# 19-AM64x-08.net
KiCad netlist of a schematic drawn in Altium Designer
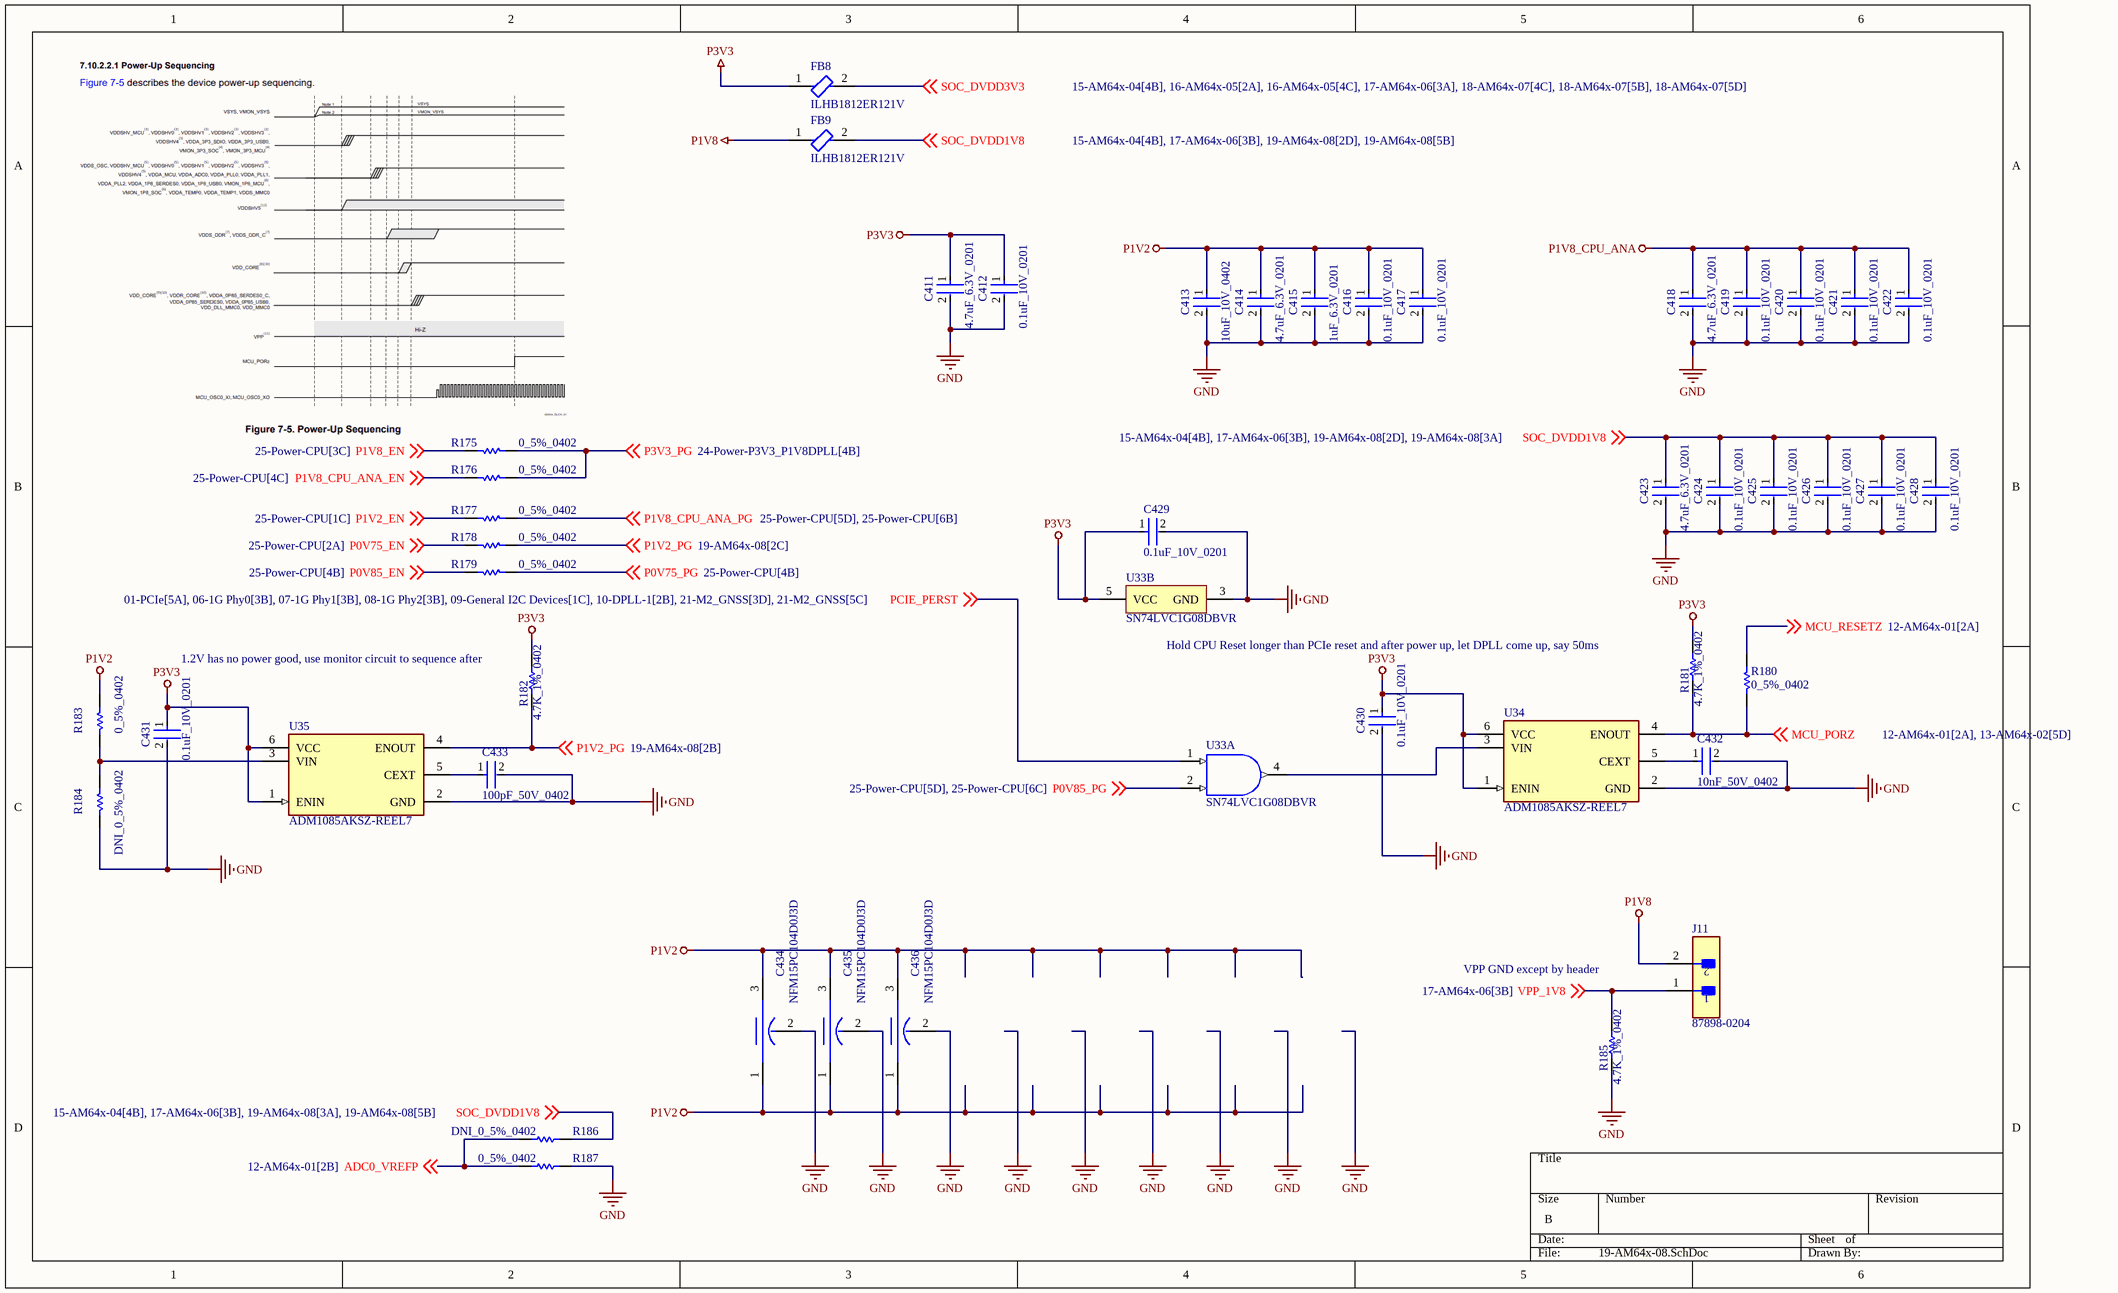
[diagram p0: 19-AM64x-08.SchDoc]

(export (version "E")
  (design (tool "Eeschema 10.0.6"))
  (components
    (comp (ref "C411")
      (value "4.7uF_6.3V_0201")
      (footprint "FP-GRM035-0_09-IPC_B")
      (description "Chip Multilayer Ceramic Capacitors for General Purpose, 0201, 4.7uF, X5R, 15%, 20%, 6.3V")
      (fields (field (name "TOLERANCE") "20%"))
      (libsource (lib "Altium Content Vault") (part "02cd4be3c70576c341d710602a673aa"))
    )
    (comp (ref "C412")
      (value "0.1uF_10V_0201")
      (footprint "FP-GRM033-0_03-IPC_C")
      (description "Chip Multilayer Ceramic Capacitors for General Purpose, 0201, 0.10uF, X5R, 15%, 10%, 10V")
      (fields (field (name "TOLERANCE") "10%") (field (name "VOLTAGE") "10V"))
      (libsource (lib "Altium Content Vault") (part "b4654b650e69147ec39a6b967a45e02"))
    )
    (comp (ref "C413")
      (value "10uF_10V_0402")
      (footprint "FP-CL05A106MP5NUNC-MFG")
      (description "CAP CER 10UF 10V X5R 0402")
      (fields
        (field (name "OCTOPART") "https://octopart.com/cl05a106mp5nunc-samsung-22457395")
        (field (name "TOLERANCE") "20%")
      )
      (libsource (lib "Altium Content Vault") (part "b4654b650e69147ec39a6b967a45e02"))
    )
    (comp (ref "C414")
      (value "4.7uF_6.3V_0201")
      (footprint "FP-GRM035-0_09-IPC_B")
      (description "Chip Multilayer Ceramic Capacitors for General Purpose, 0201, 4.7uF, X5R, 15%, 20%, 6.3V")
      (fields (field (name "TOLERANCE") "20%"))
      (libsource (lib "Altium Content Vault") (part "02cd4be3c70576c341d710602a673aa"))
    )
    (comp (ref "C415")
      (value "1uF_6.3V_0201")
      (footprint "FP-CL03-IPC_B")
      (description "Cap Ceramic 1uF 6.3V X5R ±20% Pad SMD 0201 +85°C T/R")
      (fields (field (name "TOLERANCE") "20%"))
      (libsource (lib "Altium Content Vault") (part "b4654b650e69147ec39a6b967a45e02"))
    )
    (comp (ref "C416")
      (value "0.1uF_10V_0201")
      (footprint "FP-GRM033-0_03-IPC_C")
      (description "Chip Multilayer Ceramic Capacitors for General Purpose, 0201, 0.10uF, X5R, 15%, 10%, 10V")
      (fields (field (name "TOLERANCE") "10%") (field (name "VOLTAGE") "10V"))
      (libsource (lib "Altium Content Vault") (part "b4654b650e69147ec39a6b967a45e02"))
    )
    (comp (ref "C417")
      (value "0.1uF_10V_0201")
      (footprint "FP-GRM033-0_03-IPC_C")
      (description "Chip Multilayer Ceramic Capacitors for General Purpose, 0201, 0.10uF, X5R, 15%, 10%, 10V")
      (fields (field (name "TOLERANCE") "10%") (field (name "VOLTAGE") "10V"))
      (libsource (lib "Altium Content Vault") (part "b4654b650e69147ec39a6b967a45e02"))
    )
    (comp (ref "C418")
      (value "4.7uF_6.3V_0201")
      (footprint "FP-GRM035-0_09-IPC_B")
      (description "Chip Multilayer Ceramic Capacitors for General Purpose, 0201, 4.7uF, X5R, 15%, 20%, 6.3V")
      (fields (field (name "TOLERANCE") "20%"))
      (libsource (lib "Altium Content Vault") (part "02cd4be3c70576c341d710602a673aa"))
    )
    (comp (ref "C419")
      (value "0.1uF_10V_0201")
      (footprint "FP-GRM033-0_03-IPC_C")
      (description "Chip Multilayer Ceramic Capacitors for General Purpose, 0201, 0.10uF, X5R, 15%, 10%, 10V")
      (fields (field (name "TOLERANCE") "10%") (field (name "VOLTAGE") "10V"))
      (libsource (lib "Altium Content Vault") (part "b4654b650e69147ec39a6b967a45e02"))
    )
    (comp (ref "C420")
      (value "0.1uF_10V_0201")
      (footprint "FP-GRM033-0_03-IPC_C")
      (description "Chip Multilayer Ceramic Capacitors for General Purpose, 0201, 0.10uF, X5R, 15%, 10%, 10V")
      (fields (field (name "TOLERANCE") "10%") (field (name "VOLTAGE") "10V"))
      (libsource (lib "Altium Content Vault") (part "b4654b650e69147ec39a6b967a45e02"))
    )
    (comp (ref "C421")
      (value "0.1uF_10V_0201")
      (footprint "FP-GRM033-0_03-IPC_C")
      (description "Chip Multilayer Ceramic Capacitors for General Purpose, 0201, 0.10uF, X5R, 15%, 10%, 10V")
      (fields (field (name "TOLERANCE") "10%") (field (name "VOLTAGE") "10V"))
      (libsource (lib "Altium Content Vault") (part "b4654b650e69147ec39a6b967a45e02"))
    )
    (comp (ref "C422")
      (value "0.1uF_10V_0201")
      (footprint "FP-GRM033-0_03-IPC_C")
      (description "Chip Multilayer Ceramic Capacitors for General Purpose, 0201, 0.10uF, X5R, 15%, 10%, 10V")
      (fields (field (name "TOLERANCE") "10%") (field (name "VOLTAGE") "10V"))
      (libsource (lib "Altium Content Vault") (part "b4654b650e69147ec39a6b967a45e02"))
    )
    (comp (ref "C423")
      (value "4.7uF_6.3V_0201")
      (footprint "FP-GRM035-0_09-IPC_B")
      (description "Chip Multilayer Ceramic Capacitors for General Purpose, 0201, 4.7uF, X5R, 15%, 20%, 6.3V")
      (fields (field (name "TOLERANCE") "20%"))
      (libsource (lib "Altium Content Vault") (part "02cd4be3c70576c341d710602a673aa"))
    )
    (comp (ref "C424")
      (value "0.1uF_10V_0201")
      (footprint "FP-GRM033-0_03-IPC_C")
      (description "Chip Multilayer Ceramic Capacitors for General Purpose, 0201, 0.10uF, X5R, 15%, 10%, 10V")
      (fields (field (name "TOLERANCE") "10%") (field (name "VOLTAGE") "10V"))
      (libsource (lib "Altium Content Vault") (part "b4654b650e69147ec39a6b967a45e02"))
    )
    (comp (ref "C425")
      (value "0.1uF_10V_0201")
      (footprint "FP-GRM033-0_03-IPC_C")
      (description "Chip Multilayer Ceramic Capacitors for General Purpose, 0201, 0.10uF, X5R, 15%, 10%, 10V")
      (fields (field (name "TOLERANCE") "10%") (field (name "VOLTAGE") "10V"))
      (libsource (lib "Altium Content Vault") (part "b4654b650e69147ec39a6b967a45e02"))
    )
    (comp (ref "C426")
      (value "0.1uF_10V_0201")
      (footprint "FP-GRM033-0_03-IPC_C")
      (description "Chip Multilayer Ceramic Capacitors for General Purpose, 0201, 0.10uF, X5R, 15%, 10%, 10V")
      (fields (field (name "TOLERANCE") "10%") (field (name "VOLTAGE") "10V"))
      (libsource (lib "Altium Content Vault") (part "b4654b650e69147ec39a6b967a45e02"))
    )
    (comp (ref "C427")
      (value "0.1uF_10V_0201")
      (footprint "FP-GRM033-0_03-IPC_C")
      (description "Chip Multilayer Ceramic Capacitors for General Purpose, 0201, 0.10uF, X5R, 15%, 10%, 10V")
      (fields (field (name "TOLERANCE") "10%") (field (name "VOLTAGE") "10V"))
      (libsource (lib "Altium Content Vault") (part "b4654b650e69147ec39a6b967a45e02"))
    )
    (comp (ref "C428")
      (value "0.1uF_10V_0201")
      (footprint "FP-GRM033-0_03-IPC_C")
      (description "Chip Multilayer Ceramic Capacitors for General Purpose, 0201, 0.10uF, X5R, 15%, 10%, 10V")
      (fields (field (name "TOLERANCE") "10%") (field (name "VOLTAGE") "10V"))
      (libsource (lib "Altium Content Vault") (part "b4654b650e69147ec39a6b967a45e02"))
    )
    (comp (ref "C429")
      (value "0.1uF_10V_0201")
      (footprint "FP-GRM033-0_03-IPC_C")
      (description "Chip Multilayer Ceramic Capacitors for General Purpose, 0201, 0.10uF, X5R, 15%, 10%, 10V")
      (fields (field (name "TOLERANCE") "10%") (field (name "VOLTAGE") "10V"))
      (libsource (lib "Altium Content Vault") (part "b4654b650e69147ec39a6b967a45e02"))
    )
    (comp (ref "C430")
      (value "0.1uF_10V_0201")
      (footprint "FP-GRM033-0_03-IPC_C")
      (description "Chip Multilayer Ceramic Capacitors for General Purpose, 0201, 0.10uF, X5R, 15%, 10%, 10V")
      (fields (field (name "TOLERANCE") "10%") (field (name "VOLTAGE") "10V"))
      (libsource (lib "Altium Content Vault") (part "b4654b650e69147ec39a6b967a45e02"))
    )
    (comp (ref "C431")
      (value "0.1uF_10V_0201")
      (footprint "FP-GRM033-0_03-IPC_C")
      (description "Chip Multilayer Ceramic Capacitors for General Purpose, 0201, 0.10uF, X5R, 15%, 10%, 10V")
      (fields (field (name "TOLERANCE") "10%") (field (name "VOLTAGE") "10V"))
      (libsource (lib "Altium Content Vault") (part "b4654b650e69147ec39a6b967a45e02"))
    )
    (comp (ref "C432")
      (value "10nF_50V_0402")
      (footprint "FP-CL165-IPC_C")
      (description "Cap Ceramic 10nF 50V X7R ±10% SMD 0402 +125°C Paper T/R")
      (fields (field (name "VOLTAGE") "50V") (field (name "TOLERANCE") "10%"))
      (libsource (lib "Altium Content Vault") (part "b4654b650e69147ec39a6b967a45e02"))
    )
    (comp (ref "C433")
      (value "100pF_50V_0402")
      (footprint "FP-C0402-BB-MFG")
      (description "CAP CER 100PF 50V C0G/NP0 0402")
      (fields (field (name "TOLERANCE") "0.02") (field (name "MANUFACTURER") "Kemet"))
      (libsource (lib "Altium Content Vault") (part "b4654b650e69147ec39a6b967a45e02"))
    )
    (comp (ref "C434")
      (value "NFM15PC104D0J3D")
      (footprint "FP-NFM15-0_1-MFG")
      (description "CAP FEEDTHRU 0.1UF 20% 6.3V 0402")
      (fields (field (name "TOLERANCE") "20%"))
      (libsource (lib "Altium Content Vault") (part "968ca41a07abfef6fd4f7114a56c54f"))
    )
    (comp (ref "C435")
      (value "NFM15PC104D0J3D")
      (footprint "FP-NFM15-0_1-MFG")
      (description "CAP FEEDTHRU 0.1UF 20% 6.3V 0402")
      (fields (field (name "TOLERANCE") "20%"))
      (libsource (lib "Altium Content Vault") (part "968ca41a07abfef6fd4f7114a56c54f"))
    )
    (comp (ref "C436")
      (value "NFM15PC104D0J3D")
      (footprint "FP-NFM15-0_1-MFG")
      (description "CAP FEEDTHRU 0.1UF 20% 6.3V 0402")
      (fields (field (name "TOLERANCE") "20%"))
      (libsource (lib "Altium Content Vault") (part "968ca41a07abfef6fd4f7114a56c54f"))
    )
    (comp (ref "FB8")
      (value "ILHB1812ER121V")
      (footprint "FP-ILHB1812-IPC_A")
      (description "ILHB1812ER121V Ferrite Beads Multi-Layer High Current 120Ohm 25% 100MHz 6A 20mOhm DCR 1812 T/R")
      (fields (field (name "TOLERANCE") "25%"))
      (libsource (lib "Altium Content Vault") (part "5f30dd21d616792df468990f7003faa"))
    )
    (comp (ref "FB9")
      (value "ILHB1812ER121V")
      (footprint "FP-ILHB1812-IPC_A")
      (description "ILHB1812ER121V Ferrite Beads Multi-Layer High Current 120Ohm 25% 100MHz 6A 20mOhm DCR 1812 T/R")
      (fields (field (name "TOLERANCE") "25%"))
      (libsource (lib "Altium Content Vault") (part "5f30dd21d616792df468990f7003faa"))
    )
    (comp (ref "J11")
      (value "87898-0204")
      (footprint "FP-87898-0204-MFG")
      (description "CONN BREAKAWAY SMD HDR 2POS")
      (libsource (lib "Altium Content Vault") (part "3bc925449376181038e59eaffc5286c"))
    )
    (comp (ref "R175")
      (value "0_5%_0402")
      (footprint "RESC1005X40X25LL10T10")
      (fields (field (name "MANUFACTURER") "KOA Speer") (field (name "PART NUMBER") "RK73Z1ETTP"))
      (libsource (lib "Altium Content Vault") (part "RES"))
    )
    (comp (ref "R176")
      (value "0_5%_0402")
      (footprint "RESC1005X40X25LL10T10")
      (fields (field (name "MANUFACTURER") "KOA Speer") (field (name "PART NUMBER") "RK73Z1ETTP"))
      (libsource (lib "Altium Content Vault") (part "RES"))
    )
    (comp (ref "R177")
      (value "0_5%_0402")
      (footprint "RESC1005X40X25LL10T10")
      (fields (field (name "MANUFACTURER") "KOA Speer") (field (name "PART NUMBER") "RK73Z1ETTP"))
      (libsource (lib "Altium Content Vault") (part "RES"))
    )
    (comp (ref "R178")
      (value "0_5%_0402")
      (footprint "RESC1005X40X25LL10T10")
      (fields (field (name "MANUFACTURER") "KOA Speer") (field (name "PART NUMBER") "RK73Z1ETTP"))
      (libsource (lib "Altium Content Vault") (part "RES"))
    )
    (comp (ref "R179")
      (value "0_5%_0402")
      (footprint "RESC1005X40X25LL10T10")
      (fields (field (name "MANUFACTURER") "KOA Speer") (field (name "PART NUMBER") "RK73Z1ETTP"))
      (libsource (lib "Altium Content Vault") (part "RES"))
    )
    (comp (ref "R180")
      (value "0_5%_0402")
      (footprint "RESC1005X40X25LL10T10")
      (fields (field (name "MANUFACTURER") "KOA Speer") (field (name "PART NUMBER") "RK73Z1ETTP"))
      (libsource (lib "Altium Content Vault") (part "RES"))
    )
    (comp (ref "R181")
      (value "4.7K_1%_0402")
      (footprint "RESC1005X40X25NL10T10")
      (fields (field (name "MANUFACTURER") "Bourns") (field (name "PART NUMBER") "CR0402-FX-4701GLF"))
      (libsource (lib "Altium Content Vault") (part "RES"))
    )
    (comp (ref "R182")
      (value "4.7K_1%_0402")
      (footprint "RESC1005X40X25NL10T10")
      (fields (field (name "MANUFACTURER") "Bourns") (field (name "PART NUMBER") "CR0402-FX-4701GLF"))
      (libsource (lib "Altium Content Vault") (part "RES"))
    )
    (comp (ref "R183")
      (value "0_5%_0402")
      (footprint "RESC1005X40X25LL10T10")
      (fields (field (name "MANUFACTURER") "KOA Speer") (field (name "PART NUMBER") "RK73Z1ETTP"))
      (libsource (lib "Altium Content Vault") (part "RES"))
    )
    (comp (ref "R184")
      (value "DNI_0_5%_0402")
      (footprint "RESC1005X40X25LL10T10")
      (fields (field (name "MANUFACTURER") "KOA Speer") (field (name "PART NUMBER") "RK73Z1ETTP"))
      (libsource (lib "Altium Content Vault") (part "RES"))
    )
    (comp (ref "R185")
      (value "4.7K_1%_0402")
      (footprint "RESC1005X40X25NL10T10")
      (fields (field (name "MANUFACTURER") "Bourns") (field (name "PART NUMBER") "CR0402-FX-4701GLF"))
      (libsource (lib "Altium Content Vault") (part "RES"))
    )
    (comp (ref "R186")
      (value "DNI_0_5%_0402")
      (footprint "RESC1005X40X25LL10T10")
      (fields (field (name "MANUFACTURER") "KOA Speer") (field (name "PART NUMBER") "RK73Z1ETTP"))
      (libsource (lib "Altium Content Vault") (part "RES"))
    )
    (comp (ref "R187")
      (value "0_5%_0402")
      (footprint "RESC1005X40X25LL10T10")
      (fields (field (name "MANUFACTURER") "KOA Speer") (field (name "PART NUMBER") "RK73Z1ETTP"))
      (libsource (lib "Altium Content Vault") (part "RES"))
    )
    (comp (ref "U33")
      (value "SN74LVC1G08DBVR")
      (footprint "DBV0005A_M")
      (description "Single 2-Input Positive-AND Gate, DBV0005A, LARGE T&R")
      (fields
        (field (name "GENERIC PART NUMBER") "SN74LVC1G08")
        (field (name "MANUFACTURER") "Texas Instruments")
      )
      (libsource (lib "Altium Content Vault") (part "TI-SN74XXX1X08-5"))
    )
    (comp (ref "U34")
      (value "ADM1085AKSZ-REEL7")
      (footprint "FP-KS-6-IPC_B")
      (description "IC SUPERVISOR 1 CHANNEL SC70-6")
      (libsource (lib "Altium Content Vault") (part "4d0b74b7e8e8a1541abc8f47282371d"))
    )
    (comp (ref "U35")
      (value "ADM1085AKSZ-REEL7")
      (footprint "FP-KS-6-IPC_B")
      (description "IC SUPERVISOR 1 CHANNEL SC70-6")
      (libsource (lib "Altium Content Vault") (part "4d0b74b7e8e8a1541abc8f47282371d"))
    )
  )
  (nets
    (net (code "1") (name "ADC0_VREFP") (class "Default")
      (node (ref "R186") (pin "1") (pinfunction "1_1") (pintype "passive"))
      (node (ref "R187") (pin "1") (pinfunction "1_1") (pintype "passive"))
    )
    (net (code "2") (name "GND") (class "Default")
      (node (ref "C411") (pin "2") (pinfunction "2_2") (pintype "passive"))
      (node (ref "C412") (pin "2") (pinfunction "2_2") (pintype "passive"))
      (node (ref "C413") (pin "2") (pinfunction "2_2") (pintype "passive"))
      (node (ref "C414") (pin "2") (pinfunction "2_2") (pintype "passive"))
      (node (ref "C415") (pin "2") (pinfunction "2_2") (pintype "passive"))
      (node (ref "C416") (pin "2") (pinfunction "2_2") (pintype "passive"))
      (node (ref "C417") (pin "2") (pinfunction "2_2") (pintype "passive"))
      (node (ref "C418") (pin "2") (pinfunction "2_2") (pintype "passive"))
      (node (ref "C419") (pin "2") (pinfunction "2_2") (pintype "passive"))
      (node (ref "C420") (pin "2") (pinfunction "2_2") (pintype "passive"))
      (node (ref "C421") (pin "2") (pinfunction "2_2") (pintype "passive"))
      (node (ref "C422") (pin "2") (pinfunction "2_2") (pintype "passive"))
      (node (ref "C423") (pin "2") (pinfunction "2_2") (pintype "passive"))
      (node (ref "C424") (pin "2") (pinfunction "2_2") (pintype "passive"))
      (node (ref "C425") (pin "2") (pinfunction "2_2") (pintype "passive"))
      (node (ref "C426") (pin "2") (pinfunction "2_2") (pintype "passive"))
      (node (ref "C427") (pin "2") (pinfunction "2_2") (pintype "passive"))
      (node (ref "C428") (pin "2") (pinfunction "2_2") (pintype "passive"))
      (node (ref "C429") (pin "2") (pinfunction "2_2") (pintype "passive"))
      (node (ref "C430") (pin "2") (pinfunction "2_2") (pintype "passive"))
      (node (ref "C431") (pin "2") (pinfunction "2_2") (pintype "passive"))
      (node (ref "C432") (pin "2") (pinfunction "2_2") (pintype "passive"))
      (node (ref "C433") (pin "2") (pinfunction "2_2") (pintype "passive"))
      (node (ref "C434") (pin "2") (pinfunction "GND_2") (pintype "passive"))
      (node (ref "C435") (pin "2") (pinfunction "GND_2") (pintype "passive"))
      (node (ref "C436") (pin "2") (pinfunction "GND_2") (pintype "passive"))
      (node (ref "R184") (pin "2") (pinfunction "2_2") (pintype "passive"))
      (node (ref "R185") (pin "2") (pinfunction "2_2") (pintype "passive"))
      (node (ref "R187") (pin "2") (pinfunction "2_2") (pintype "passive"))
      (node (ref "U33") (pin "3") (pinfunction "GND_3") (pintype "power_in"))
      (node (ref "U34") (pin "2") (pinfunction "GND_2") (pintype "power_in"))
      (node (ref "U35") (pin "2") (pinfunction "GND_2") (pintype "power_in"))
    )
    (net (code "3") (name "MCU_PORZ") (class "Default")
      (node (ref "R180") (pin "2") (pinfunction "2_2") (pintype "passive"))
      (node (ref "R181") (pin "2") (pinfunction "2_2") (pintype "passive"))
      (node (ref "U34") (pin "4") (pinfunction "ENOUT_4") (pintype "open_collector"))
    )
    (net (code "4") (name "MCU_RESETZ") (class "Default")
      (node (ref "R180") (pin "1") (pinfunction "1_1") (pintype "passive"))
    )
    (net (code "5") (name "Net-(U33A-Y)") (class "Default")
      (node (ref "U33") (pin "4") (pinfunction "Y_4") (pintype "output"))
      (node (ref "U34") (pin "3") (pinfunction "VIN_3") (pintype "power_in"))
    )
    (net (code "6") (name "Net-(U34-CEXT)") (class "Default")
      (node (ref "C432") (pin "1") (pinfunction "1_1") (pintype "passive"))
      (node (ref "U34") (pin "5") (pinfunction "CEXT_5") (pintype "passive"))
    )
    (net (code "7") (name "Net-(U35-CEXT)") (class "Default")
      (node (ref "C433") (pin "1") (pinfunction "1_1") (pintype "passive"))
      (node (ref "U35") (pin "5") (pinfunction "CEXT_5") (pintype "passive"))
    )
    (net (code "8") (name "Net-(U35-VIN)") (class "Default")
      (node (ref "R183") (pin "2") (pinfunction "2_2") (pintype "passive"))
      (node (ref "R184") (pin "1") (pinfunction "1_1") (pintype "passive"))
      (node (ref "U35") (pin "3") (pinfunction "VIN_3") (pintype "power_in"))
    )
    (net (code "9") (name "P0V75_EN") (class "Default")
      (node (ref "R178") (pin "2") (pinfunction "2_2") (pintype "passive"))
    )
    (net (code "10") (name "P0V75_PG") (class "Default")
      (node (ref "R179") (pin "1") (pinfunction "1_1") (pintype "passive"))
    )
    (net (code "11") (name "P0V85_EN") (class "Default")
      (node (ref "R179") (pin "2") (pinfunction "2_2") (pintype "passive"))
    )
    (net (code "12") (name "P0V85_PG") (class "Default")
      (node (ref "U33") (pin "2") (pinfunction "B_2") (pintype "input"))
    )
    (net (code "13") (name "P1V2") (class "Default")
      (node (ref "C413") (pin "1") (pinfunction "1_1") (pintype "passive"))
      (node (ref "C414") (pin "1") (pinfunction "1_1") (pintype "passive"))
      (node (ref "C415") (pin "1") (pinfunction "1_1") (pintype "passive"))
      (node (ref "C416") (pin "1") (pinfunction "1_1") (pintype "passive"))
      (node (ref "C417") (pin "1") (pinfunction "1_1") (pintype "passive"))
      (node (ref "C434") (pin "1") (pinfunction "Input_1") (pintype "passive"))
      (node (ref "C434") (pin "3") (pinfunction "Output_3") (pintype "passive"))
      (node (ref "C435") (pin "1") (pinfunction "Input_1") (pintype "passive"))
      (node (ref "C435") (pin "3") (pinfunction "Output_3") (pintype "passive"))
      (node (ref "C436") (pin "1") (pinfunction "Input_1") (pintype "passive"))
      (node (ref "C436") (pin "3") (pinfunction "Output_3") (pintype "passive"))
      (node (ref "R183") (pin "1") (pinfunction "1_1") (pintype "passive"))
    )
    (net (code "14") (name "P1V2_EN") (class "Default")
      (node (ref "R177") (pin "2") (pinfunction "2_2") (pintype "passive"))
    )
    (net (code "15") (name "P1V2_PG") (class "Default")
      (node (ref "R178") (pin "1") (pinfunction "1_1") (pintype "passive"))
      (node (ref "R182") (pin "2") (pinfunction "2_2") (pintype "passive"))
      (node (ref "U35") (pin "4") (pinfunction "ENOUT_4") (pintype "open_collector"))
    )
    (net (code "16") (name "P1V8") (class "Default")
      (node (ref "FB9") (pin "1") (pinfunction "1_1") (pintype "passive"))
      (node (ref "J11") (pin "2") (pinfunction "2_2") (pintype "passive"))
    )
    (net (code "17") (name "P1V8_CPU_ANA") (class "Default")
      (node (ref "C418") (pin "1") (pinfunction "1_1") (pintype "passive"))
      (node (ref "C419") (pin "1") (pinfunction "1_1") (pintype "passive"))
      (node (ref "C420") (pin "1") (pinfunction "1_1") (pintype "passive"))
      (node (ref "C421") (pin "1") (pinfunction "1_1") (pintype "passive"))
      (node (ref "C422") (pin "1") (pinfunction "1_1") (pintype "passive"))
    )
    (net (code "18") (name "P1V8_CPU_ANA_EN") (class "Default")
      (node (ref "R176") (pin "2") (pinfunction "2_2") (pintype "passive"))
    )
    (net (code "19") (name "P1V8_CPU_ANA_PG") (class "Default")
      (node (ref "R177") (pin "1") (pinfunction "1_1") (pintype "passive"))
    )
    (net (code "20") (name "P1V8_EN") (class "Default")
      (node (ref "R175") (pin "2") (pinfunction "2_2") (pintype "passive"))
    )
    (net (code "21") (name "P3V3") (class "Default")
      (node (ref "C411") (pin "1") (pinfunction "1_1") (pintype "passive"))
      (node (ref "C412") (pin "1") (pinfunction "1_1") (pintype "passive"))
      (node (ref "C429") (pin "1") (pinfunction "1_1") (pintype "passive"))
      (node (ref "C430") (pin "1") (pinfunction "1_1") (pintype "passive"))
      (node (ref "C431") (pin "1") (pinfunction "1_1") (pintype "passive"))
      (node (ref "FB8") (pin "1") (pinfunction "1_1") (pintype "passive"))
      (node (ref "R181") (pin "1") (pinfunction "1_1") (pintype "passive"))
      (node (ref "R182") (pin "1") (pinfunction "1_1") (pintype "passive"))
      (node (ref "U33") (pin "5") (pinfunction "VCC_5") (pintype "power_in"))
      (node (ref "U34") (pin "1") (pinfunction "ENIN_1") (pintype "input"))
      (node (ref "U34") (pin "6") (pinfunction "VCC_6") (pintype "power_in"))
      (node (ref "U35") (pin "1") (pinfunction "ENIN_1") (pintype "input"))
      (node (ref "U35") (pin "6") (pinfunction "VCC_6") (pintype "power_in"))
    )
    (net (code "22") (name "P3V3_PG") (class "Default")
      (node (ref "R175") (pin "1") (pinfunction "1_1") (pintype "passive"))
      (node (ref "R176") (pin "1") (pinfunction "1_1") (pintype "passive"))
    )
    (net (code "23") (name "PCIE_PERST") (class "Default")
      (node (ref "U33") (pin "1") (pinfunction "A_1") (pintype "input"))
    )
    (net (code "24") (name "SOC_DVDD1V8") (class "Default")
      (node (ref "C423") (pin "1") (pinfunction "1_1") (pintype "passive"))
      (node (ref "C424") (pin "1") (pinfunction "1_1") (pintype "passive"))
      (node (ref "C425") (pin "1") (pinfunction "1_1") (pintype "passive"))
      (node (ref "C426") (pin "1") (pinfunction "1_1") (pintype "passive"))
      (node (ref "C427") (pin "1") (pinfunction "1_1") (pintype "passive"))
      (node (ref "C428") (pin "1") (pinfunction "1_1") (pintype "passive"))
      (node (ref "FB9") (pin "2") (pinfunction "2_2") (pintype "passive"))
      (node (ref "R186") (pin "2") (pinfunction "2_2") (pintype "passive"))
    )
    (net (code "25") (name "SOC_DVDD3V3") (class "Default")
      (node (ref "FB8") (pin "2") (pinfunction "2_2") (pintype "passive"))
    )
    (net (code "26") (name "VPP_1V8") (class "Default")
      (node (ref "J11") (pin "1") (pinfunction "1_1") (pintype "passive"))
      (node (ref "R185") (pin "1") (pinfunction "1_1") (pintype "passive"))
    )
  )
)
